# node.net
KiCad netlist of a schematic drawn in EAGLE
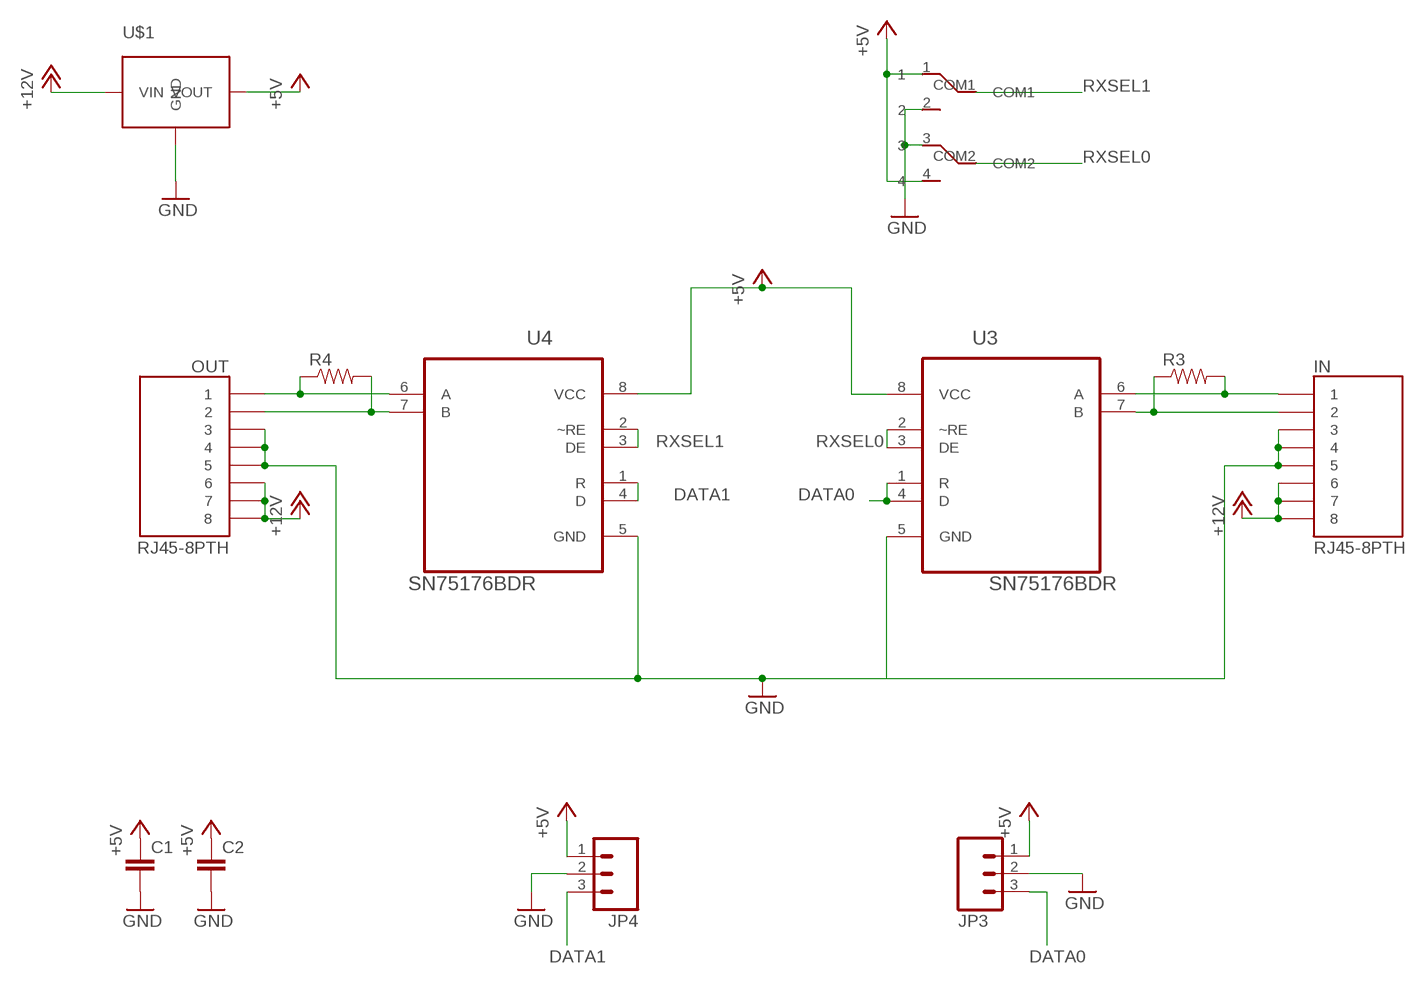
[diagram p0: schematic, sheet 1]

(export (version "E")
  (design (tool "Eeschema 10.0.6"))
  (components
    (comp (ref "C1")
      (value "CAPPTH1")
      (footprint "eagle-import:CAP-PTH-5MM")
      (libsource (lib "eagle-import") (part "CAPPTH1"))
    )
    (comp (ref "C2")
      (value "CAPPTH1")
      (footprint "eagle-import:CAP-PTH-5MM")
      (libsource (lib "eagle-import") (part "CAPPTH1"))
    )
    (comp (ref "IN")
      (value "RJ45-8PTH")
      (footprint "eagle-import:RJ45-8")
      (libsource (lib "eagle-import") (part "RJ45-8PTH"))
    )
    (comp (ref "JP3")
      (value "M03JST-PTH")
      (footprint "eagle-import:JST-3-PTH")
      (libsource (lib "eagle-import") (part "M03JST-PTH"))
    )
    (comp (ref "JP4")
      (value "M03JST-PTH")
      (footprint "eagle-import:JST-3-PTH")
      (libsource (lib "eagle-import") (part "M03JST-PTH"))
    )
    (comp (ref "OUT")
      (value "RJ45-8PTH")
      (footprint "eagle-import:RJ45-8")
      (libsource (lib "eagle-import") (part "RJ45-8PTH"))
    )
    (comp (ref "R3")
      (value "RESISTORPTH-1/2W")
      (footprint "eagle-import:AXIAL-0.5")
      (libsource (lib "eagle-import") (part "RESISTORPTH-1/2W"))
    )
    (comp (ref "R4")
      (value "RESISTORPTH-1/2W")
      (footprint "eagle-import:AXIAL-0.5")
      (libsource (lib "eagle-import") (part "RESISTORPTH-1/2W"))
    )
    (comp (ref "U$1")
      (value "TSR1-2450")
      (footprint "eagle-import:TSR-1")
      (libsource (lib "eagle-import") (part "TSR1-2450"))
    )
    (comp (ref "U$2")
      (value "SWITCH-NKK-DPDT")
      (footprint "eagle-import:SWITCH-NKK-DPDT")
      (libsource (lib "eagle-import") (part "SWITCH-NKK-DPDT"))
    )
    (comp (ref "U3")
      (value "SN75176BDR")
      (footprint "eagle-import:SOIC127P600X175-8N")
      (libsource (lib "eagle-import") (part "SN75176BDR"))
    )
    (comp (ref "U4")
      (value "SN75176BDR")
      (footprint "eagle-import:SOIC127P600X175-8N")
      (libsource (lib "eagle-import") (part "SN75176BDR"))
    )
  )
  (nets
    (net (code "1") (name "+5V") (class "Default")
      (node (ref "C1") (pin "1") (pinfunction "1_1") (pintype "passive"))
      (node (ref "C2") (pin "1") (pinfunction "1_1") (pintype "passive"))
      (node (ref "JP3") (pin "1") (pinfunction "1_1") (pintype "passive"))
      (node (ref "JP4") (pin "1") (pinfunction "1_1") (pintype "passive"))
      (node (ref "U$1") (pin "3") (pinfunction "VOUT_3") (pintype "power_in"))
      (node (ref "U$2") (pin "1") (pinfunction "1_1") (pintype "bidirectional"))
      (node (ref "U$2") (pin "4") (pinfunction "4_4") (pintype "bidirectional"))
      (node (ref "U3") (pin "8") (pinfunction "VCC_8") (pintype "power_in"))
      (node (ref "U4") (pin "8") (pinfunction "VCC_8") (pintype "power_in"))
    )
    (net (code "2") (name "+12V") (class "Default")
      (node (ref "IN") (pin "6") (pinfunction "6_6") (pintype "bidirectional"))
      (node (ref "IN") (pin "7") (pinfunction "7_7") (pintype "bidirectional"))
      (node (ref "IN") (pin "8") (pinfunction "8_8") (pintype "bidirectional"))
      (node (ref "OUT") (pin "6") (pinfunction "6_6") (pintype "bidirectional"))
      (node (ref "OUT") (pin "7") (pinfunction "7_7") (pintype "bidirectional"))
      (node (ref "OUT") (pin "8") (pinfunction "8_8") (pintype "bidirectional"))
      (node (ref "U$1") (pin "1") (pinfunction "VIN_1") (pintype "power_in"))
    )
    (net (code "3") (name "/DATA0") (class "Default")
      (node (ref "JP3") (pin "3") (pinfunction "3_3") (pintype "passive"))
      (node (ref "U3") (pin "1") (pinfunction "R_1") (pintype "input"))
      (node (ref "U3") (pin "4") (pinfunction "D_4") (pintype "input"))
    )
    (net (code "4") (name "/DATA1") (class "Default")
      (node (ref "JP4") (pin "3") (pinfunction "3_3") (pintype "passive"))
      (node (ref "U4") (pin "1") (pinfunction "R_1") (pintype "input"))
      (node (ref "U4") (pin "4") (pinfunction "D_4") (pintype "input"))
    )
    (net (code "5") (name "/RXSEL0") (class "Default")
      (node (ref "U$2") (pin "COM2") (pinfunction "COM2_COM2") (pintype "bidirectional"))
      (node (ref "U3") (pin "2") (pinfunction "~{RE}_2") (pintype "input"))
      (node (ref "U3") (pin "3") (pinfunction "DE_3") (pintype "input"))
    )
    (net (code "6") (name "/RXSEL1") (class "Default")
      (node (ref "U$2") (pin "COM1") (pinfunction "COM1_COM1") (pintype "bidirectional"))
      (node (ref "U4") (pin "2") (pinfunction "~{RE}_2") (pintype "input"))
      (node (ref "U4") (pin "3") (pinfunction "DE_3") (pintype "input"))
    )
    (net (code "7") (name "GND") (class "Default")
      (node (ref "C1") (pin "2") (pinfunction "2_2") (pintype "passive"))
      (node (ref "C2") (pin "2") (pinfunction "2_2") (pintype "passive"))
      (node (ref "IN") (pin "3") (pinfunction "3_3") (pintype "bidirectional"))
      (node (ref "IN") (pin "4") (pinfunction "4_4") (pintype "bidirectional"))
      (node (ref "IN") (pin "5") (pinfunction "5_5") (pintype "bidirectional"))
      (node (ref "JP3") (pin "2") (pinfunction "2_2") (pintype "passive"))
      (node (ref "JP4") (pin "2") (pinfunction "2_2") (pintype "passive"))
      (node (ref "OUT") (pin "3") (pinfunction "3_3") (pintype "bidirectional"))
      (node (ref "OUT") (pin "4") (pinfunction "4_4") (pintype "bidirectional"))
      (node (ref "OUT") (pin "5") (pinfunction "5_5") (pintype "bidirectional"))
      (node (ref "U$1") (pin "2") (pinfunction "GND_2") (pintype "power_in"))
      (node (ref "U$2") (pin "2") (pinfunction "2_2") (pintype "bidirectional"))
      (node (ref "U$2") (pin "3") (pinfunction "3_3") (pintype "bidirectional"))
      (node (ref "U3") (pin "5") (pinfunction "GND_5") (pintype "passive"))
      (node (ref "U4") (pin "5") (pinfunction "GND_5") (pintype "passive"))
    )
    (net (code "8") (name "Net-(R3-1)") (class "Default")
      (node (ref "IN") (pin "2") (pinfunction "2_2") (pintype "bidirectional"))
      (node (ref "R3") (pin "P$1") (pinfunction "1_P$1") (pintype "passive"))
      (node (ref "U3") (pin "7") (pinfunction "B_7") (pintype "output"))
    )
    (net (code "9") (name "Net-(R3-2)") (class "Default")
      (node (ref "IN") (pin "1") (pinfunction "1_1") (pintype "bidirectional"))
      (node (ref "R3") (pin "P$2") (pinfunction "2_P$2") (pintype "passive"))
      (node (ref "U3") (pin "6") (pinfunction "A_6") (pintype "output"))
    )
    (net (code "10") (name "Net-(R4-1)") (class "Default")
      (node (ref "OUT") (pin "1") (pinfunction "1_1") (pintype "bidirectional"))
      (node (ref "R4") (pin "P$1") (pinfunction "1_P$1") (pintype "passive"))
      (node (ref "U4") (pin "6") (pinfunction "A_6") (pintype "output"))
    )
    (net (code "11") (name "Net-(R4-2)") (class "Default")
      (node (ref "OUT") (pin "2") (pinfunction "2_2") (pintype "bidirectional"))
      (node (ref "R4") (pin "P$2") (pinfunction "2_P$2") (pintype "passive"))
      (node (ref "U4") (pin "7") (pinfunction "B_7") (pintype "output"))
    )
  )
)
